# layer1v1.net
KiCad netlist of a schematic drawn in EAGLE
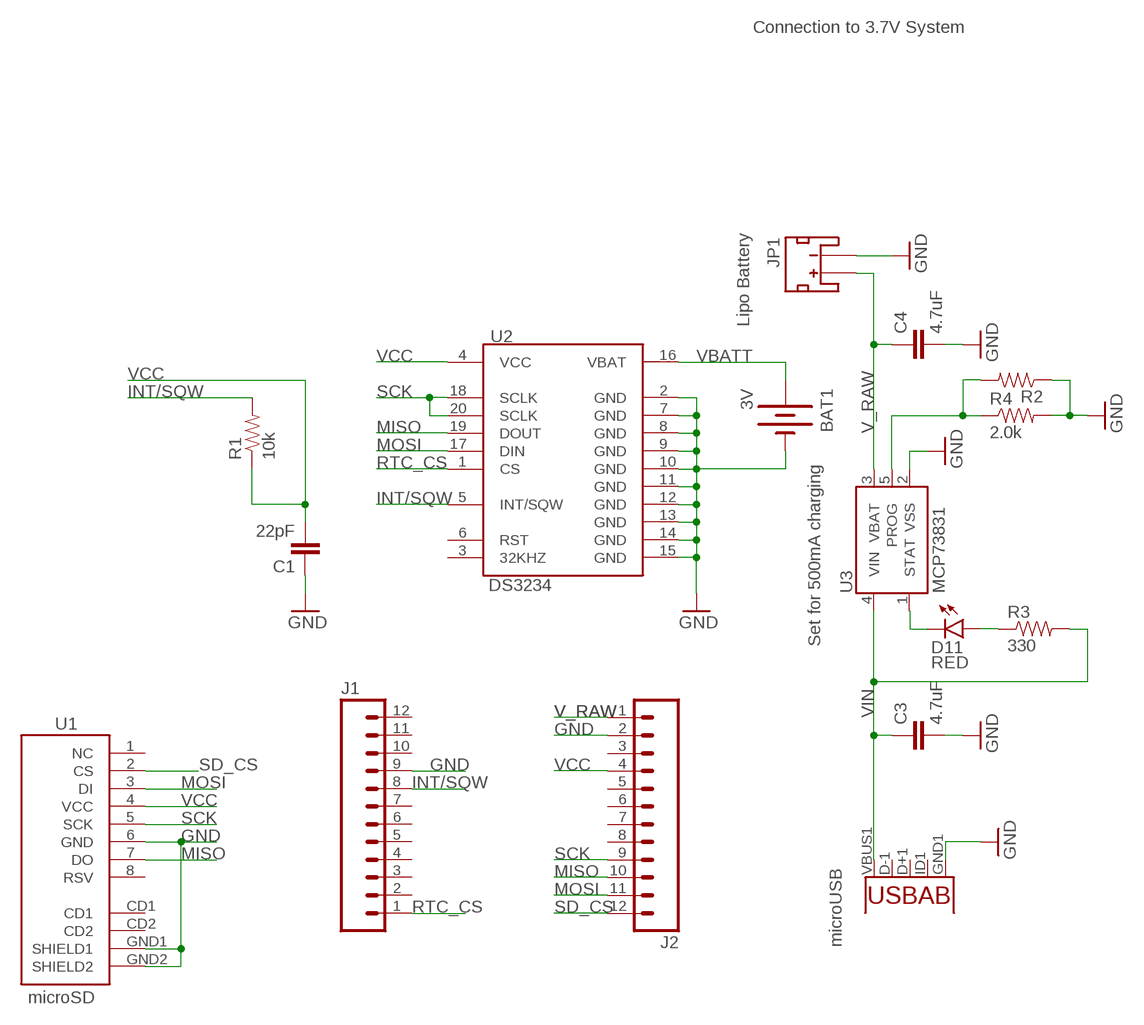
[diagram p0: schematic, sheet 1]

(export (version "E")
  (design (tool "Eeschema 10.0.6"))
  (components
    (comp (ref "BAT1")
      (value "3V")
      (footprint "eagle-import:BATTCON_12MM_CURVED")
      (libsource (lib "eagle-import") (part "BATTERY"))
    )
    (comp (ref "C1")
      (value "22pF")
      (footprint "eagle-import:0402-CAP")
      (libsource (lib "eagle-import") (part "CAP0402-CAP"))
    )
    (comp (ref "C3")
      (value "4.7uF")
      (footprint "eagle-import:0603-CAP")
      (libsource (lib "eagle-import") (part "4.7UF-6.3V-10%(0603)0603"))
    )
    (comp (ref "C4")
      (value "4.7uF")
      (footprint "eagle-import:0603-CAP")
      (libsource (lib "eagle-import") (part "4.7UF-6.3V-10%(0603)0603"))
    )
    (comp (ref "D11")
      (value "RED")
      (footprint "eagle-import:LED-0603")
      (libsource (lib "eagle-import") (part "LED-RED0603"))
    )
    (comp (ref "J1")
      (value "M12PTH")
      (footprint "eagle-import:1X12")
      (libsource (lib "eagle-import") (part "M12PTH"))
    )
    (comp (ref "J2")
      (value "M12PTH")
      (footprint "eagle-import:1X12")
      (libsource (lib "eagle-import") (part "M12PTH"))
    )
    (comp (ref "JP1")
      (value "JST")
      (footprint "eagle-import:JST-2-SMD")
      (libsource (lib "eagle-import") (part "JST_2MM_MALE"))
    )
    (comp (ref "JP9")
      (value "Micro USB")
      (footprint "eagle-import:USB-AB-MICRO-SMD_V03")
      (libsource (lib "eagle-import") (part "USB-ABCONN-11794"))
    )
    (comp (ref "R1")
      (value "10k")
      (footprint "eagle-import:0402-RES")
      (libsource (lib "eagle-import") (part "RESISTOR0402-RES"))
    )
    (comp (ref "R2")
      (value "RESISTORPTH-1/4W-VERT-KIT")
      (footprint "eagle-import:AXIAL-0.1EZ")
      (libsource (lib "eagle-import") (part "RESISTORPTH-1/4W-VERT-KIT"))
    )
    (comp (ref "R3")
      (value "330")
      (footprint "eagle-import:0603-RES")
      (libsource (lib "eagle-import") (part "330OHM1/10W1%(0603)"))
    )
    (comp (ref "R4")
      (value "2.0k")
      (footprint "eagle-import:0603-RES")
      (libsource (lib "eagle-import") (part "2.0KOHM1/10W5%(0603)"))
    )
    (comp (ref "U1")
      (value "microSD")
      (footprint "eagle-import:MICRO-SD-SOCKET-PP")
      (libsource (lib "eagle-import") (part "USD-SOCKETSMD"))
    )
    (comp (ref "U2")
      (value "DS3234")
      (footprint "eagle-import:DS3234")
      (libsource (lib "eagle-import") (part "DS3234"))
    )
    (comp (ref "U3")
      (value "MCP73831")
      (footprint "eagle-import:SOT23-5")
      (libsource (lib "eagle-import") (part "MCP73831"))
    )
  )
  (nets
    (net (code "1") (name "/INT{slash}SQW") (class "Default")
      (node (ref "J1") (pin "8") (pinfunction "8_8") (pintype "passive"))
      (node (ref "R1") (pin "2") (pinfunction "2_2") (pintype "passive"))
      (node (ref "U2") (pin "5") (pinfunction "INT/SQW_5") (pintype "bidirectional"))
    )
    (net (code "2") (name "/MISO") (class "Default")
      (node (ref "J2") (pin "10") (pinfunction "10_10") (pintype "passive"))
      (node (ref "U1") (pin "7") (pinfunction "DO_7") (pintype "bidirectional"))
      (node (ref "U2") (pin "19") (pinfunction "DOUT_19") (pintype "bidirectional"))
    )
    (net (code "3") (name "/MOSI") (class "Default")
      (node (ref "J2") (pin "11") (pinfunction "11_11") (pintype "passive"))
      (node (ref "U1") (pin "3") (pinfunction "DI_3") (pintype "bidirectional"))
      (node (ref "U2") (pin "17") (pinfunction "DIN_17") (pintype "bidirectional"))
    )
    (net (code "4") (name "/RTC_CS") (class "Default")
      (node (ref "J1") (pin "1") (pinfunction "1_1") (pintype "passive"))
      (node (ref "U2") (pin "1") (pinfunction "CS_1") (pintype "bidirectional"))
    )
    (net (code "5") (name "/SCK") (class "Default")
      (node (ref "J2") (pin "9") (pinfunction "9_9") (pintype "passive"))
      (node (ref "U1") (pin "5") (pinfunction "SCK_5") (pintype "bidirectional"))
      (node (ref "U2") (pin "18") (pinfunction "SCLK_18") (pintype "bidirectional"))
      (node (ref "U2") (pin "20") (pinfunction "SCLK_20") (pintype "bidirectional"))
    )
    (net (code "6") (name "/SD_CS") (class "Default")
      (node (ref "J2") (pin "12") (pinfunction "12_12") (pintype "passive"))
      (node (ref "U1") (pin "2") (pinfunction "CS_2") (pintype "bidirectional"))
    )
    (net (code "7") (name "/VBATT") (class "Default")
      (node (ref "BAT1") (pin "PWR@1") (pinfunction "+_PWR@1") (pintype "power_in"))
      (node (ref "U2") (pin "16") (pinfunction "VBAT_16") (pintype "bidirectional"))
    )
    (net (code "8") (name "/VCC") (class "Default")
      (node (ref "C1") (pin "2") (pinfunction "2_2") (pintype "passive"))
      (node (ref "J2") (pin "4") (pinfunction "4_4") (pintype "passive"))
      (node (ref "R1") (pin "1") (pinfunction "1_1") (pintype "passive"))
      (node (ref "U1") (pin "4") (pinfunction "VCC_4") (pintype "bidirectional"))
      (node (ref "U2") (pin "4") (pinfunction "VCC_4") (pintype "bidirectional"))
    )
    (net (code "9") (name "/VIN") (class "Default")
      (node (ref "C3") (pin "1") (pinfunction "1_1") (pintype "passive"))
      (node (ref "JP9") (pin "VBUS1") (pinfunction "VBUS_VBUS1") (pintype "bidirectional"))
      (node (ref "R3") (pin "2") (pinfunction "2_2") (pintype "passive"))
      (node (ref "U3") (pin "4") (pinfunction "VIN_4") (pintype "power_in"))
    )
    (net (code "10") (name "/V_RAW") (class "Default")
      (node (ref "C4") (pin "1") (pinfunction "1_1") (pintype "passive"))
      (node (ref "J2") (pin "1") (pinfunction "1_1") (pintype "passive"))
      (node (ref "JP1") (pin "2") (pinfunction "+_2") (pintype "bidirectional"))
      (node (ref "U3") (pin "3") (pinfunction "VBAT_3") (pintype "power_in"))
    )
    (net (code "11") (name "GND") (class "Default")
      (node (ref "BAT1") (pin "GND") (pinfunction "-_GND") (pintype "power_in"))
      (node (ref "C1") (pin "1") (pinfunction "1_1") (pintype "passive"))
      (node (ref "C3") (pin "2") (pinfunction "2_2") (pintype "passive"))
      (node (ref "C4") (pin "2") (pinfunction "2_2") (pintype "passive"))
      (node (ref "J1") (pin "9") (pinfunction "9_9") (pintype "passive"))
      (node (ref "J2") (pin "2") (pinfunction "2_2") (pintype "passive"))
      (node (ref "JP1") (pin "1") (pinfunction "-_1") (pintype "bidirectional"))
      (node (ref "JP9") (pin "GND1") (pinfunction "GND_GND1") (pintype "bidirectional"))
      (node (ref "R2") (pin "P$1") (pinfunction "1_P$1") (pintype "passive"))
      (node (ref "R4") (pin "2") (pinfunction "2_2") (pintype "passive"))
      (node (ref "U1") (pin "6") (pinfunction "GND_6") (pintype "bidirectional"))
      (node (ref "U1") (pin "GND1") (pinfunction "SHIELD1_GND1") (pintype "bidirectional"))
      (node (ref "U1") (pin "GND2") (pinfunction "SHIELD2_GND2") (pintype "bidirectional"))
      (node (ref "U2") (pin "10") (pinfunction "GND_10") (pintype "bidirectional"))
      (node (ref "U2") (pin "11") (pinfunction "GND_11") (pintype "bidirectional"))
      (node (ref "U2") (pin "12") (pinfunction "GND_12") (pintype "bidirectional"))
      (node (ref "U2") (pin "13") (pinfunction "GND_13") (pintype "bidirectional"))
      (node (ref "U2") (pin "14") (pinfunction "GND_14") (pintype "bidirectional"))
      (node (ref "U2") (pin "15") (pinfunction "GND_15") (pintype "bidirectional"))
      (node (ref "U2") (pin "2") (pinfunction "GND_2") (pintype "bidirectional"))
      (node (ref "U2") (pin "7") (pinfunction "GND_7") (pintype "bidirectional"))
      (node (ref "U2") (pin "8") (pinfunction "GND_8") (pintype "bidirectional"))
      (node (ref "U2") (pin "9") (pinfunction "GND_9") (pintype "bidirectional"))
      (node (ref "U3") (pin "2") (pinfunction "VSS_2") (pintype "power_in"))
    )
    (net (code "12") (name "Net-(D11-PadA)") (class "Default")
      (node (ref "D11") (pin "A") (pinfunction "A_A") (pintype "passive"))
      (node (ref "R3") (pin "1") (pinfunction "1_1") (pintype "passive"))
    )
    (net (code "13") (name "Net-(R2-2)") (class "Default")
      (node (ref "R2") (pin "P$2") (pinfunction "2_P$2") (pintype "passive"))
      (node (ref "R4") (pin "1") (pinfunction "1_1") (pintype "passive"))
      (node (ref "U3") (pin "5") (pinfunction "PROG_5") (pintype "input"))
    )
    (net (code "14") (name "Net-(U3-STAT)") (class "Default")
      (node (ref "D11") (pin "C") (pinfunction "C_C") (pintype "passive"))
      (node (ref "U3") (pin "1") (pinfunction "STAT_1") (pintype "output"))
    )
    (net (code "15") (name "unconnected-(J1-Pad2)") (class "Default")
      (node (ref "J1") (pin "2") (pinfunction "2_2") (pintype "passive"))
    )
    (net (code "16") (name "unconnected-(J1-Pad3)") (class "Default")
      (node (ref "J1") (pin "3") (pinfunction "3_3") (pintype "passive"))
    )
    (net (code "17") (name "unconnected-(J1-Pad4)") (class "Default")
      (node (ref "J1") (pin "4") (pinfunction "4_4") (pintype "passive"))
    )
    (net (code "18") (name "unconnected-(J1-Pad5)") (class "Default")
      (node (ref "J1") (pin "5") (pinfunction "5_5") (pintype "passive"))
    )
    (net (code "19") (name "unconnected-(J1-Pad6)") (class "Default")
      (node (ref "J1") (pin "6") (pinfunction "6_6") (pintype "passive"))
    )
    (net (code "20") (name "unconnected-(J1-Pad7)") (class "Default")
      (node (ref "J1") (pin "7") (pinfunction "7_7") (pintype "passive"))
    )
    (net (code "21") (name "unconnected-(J1-Pad10)") (class "Default")
      (node (ref "J1") (pin "10") (pinfunction "10_10") (pintype "passive"))
    )
    (net (code "22") (name "unconnected-(J1-Pad11)") (class "Default")
      (node (ref "J1") (pin "11") (pinfunction "11_11") (pintype "passive"))
    )
    (net (code "23") (name "unconnected-(J1-Pad12)") (class "Default")
      (node (ref "J1") (pin "12") (pinfunction "12_12") (pintype "passive"))
    )
    (net (code "24") (name "unconnected-(J2-Pad3)") (class "Default")
      (node (ref "J2") (pin "3") (pinfunction "3_3") (pintype "passive"))
    )
    (net (code "25") (name "unconnected-(J2-Pad5)") (class "Default")
      (node (ref "J2") (pin "5") (pinfunction "5_5") (pintype "passive"))
    )
    (net (code "26") (name "unconnected-(J2-Pad6)") (class "Default")
      (node (ref "J2") (pin "6") (pinfunction "6_6") (pintype "passive"))
    )
    (net (code "27") (name "unconnected-(J2-Pad7)") (class "Default")
      (node (ref "J2") (pin "7") (pinfunction "7_7") (pintype "passive"))
    )
    (net (code "28") (name "unconnected-(J2-Pad8)") (class "Default")
      (node (ref "J2") (pin "8") (pinfunction "8_8") (pintype "passive"))
    )
    (net (code "29") (name "unconnected-(JP1-PAD1-PadNC1)") (class "Default")
      (node (ref "JP1") (pin "NC1") (pinfunction "PAD1_NC1") (pintype "bidirectional"))
    )
    (net (code "30") (name "unconnected-(JP1-PAD2-PadNC2)") (class "Default")
      (node (ref "JP1") (pin "NC2") (pinfunction "PAD2_NC2") (pintype "bidirectional"))
    )
    (net (code "31") (name "unconnected-(JP9-D+-PadD+1)") (class "Default")
      (node (ref "JP9") (pin "D+1") (pinfunction "D+_D+1") (pintype "bidirectional"))
    )
    (net (code "32") (name "unconnected-(JP9-D--PadD-1)") (class "Default")
      (node (ref "JP9") (pin "D-1") (pinfunction "D-_D-1") (pintype "bidirectional"))
    )
    (net (code "33") (name "unconnected-(JP9-USBID-PadID1)") (class "Default")
      (node (ref "JP9") (pin "ID1") (pinfunction "USBID_ID1") (pintype "bidirectional"))
    )
    (net (code "34") (name "unconnected-(U1-NC-Pad1)") (class "Default")
      (node (ref "U1") (pin "1") (pinfunction "NC_1") (pintype "bidirectional"))
    )
    (net (code "35") (name "unconnected-(U1-PadCD1)") (class "Default")
      (node (ref "U1") (pin "CD1") (pinfunction "CD1_CD1") (pintype "bidirectional"))
    )
    (net (code "36") (name "unconnected-(U1-PadCD2)") (class "Default")
      (node (ref "U1") (pin "CD2") (pinfunction "CD2_CD2") (pintype "bidirectional"))
    )
    (net (code "37") (name "unconnected-(U1-RSV-Pad8)") (class "Default")
      (node (ref "U1") (pin "8") (pinfunction "RSV_8") (pintype "bidirectional"))
    )
    (net (code "38") (name "unconnected-(U2-32KHZ-Pad3)") (class "Default")
      (node (ref "U2") (pin "3") (pinfunction "32KHZ_3") (pintype "bidirectional"))
    )
    (net (code "39") (name "unconnected-(U2-RST-Pad6)") (class "Default")
      (node (ref "U2") (pin "6") (pinfunction "RST_6") (pintype "bidirectional"))
    )
  )
)
